# DM1098LUXD-LITE_RIGHT_OV7251.net
KiCad netlist of a schematic drawn in Altium Designer
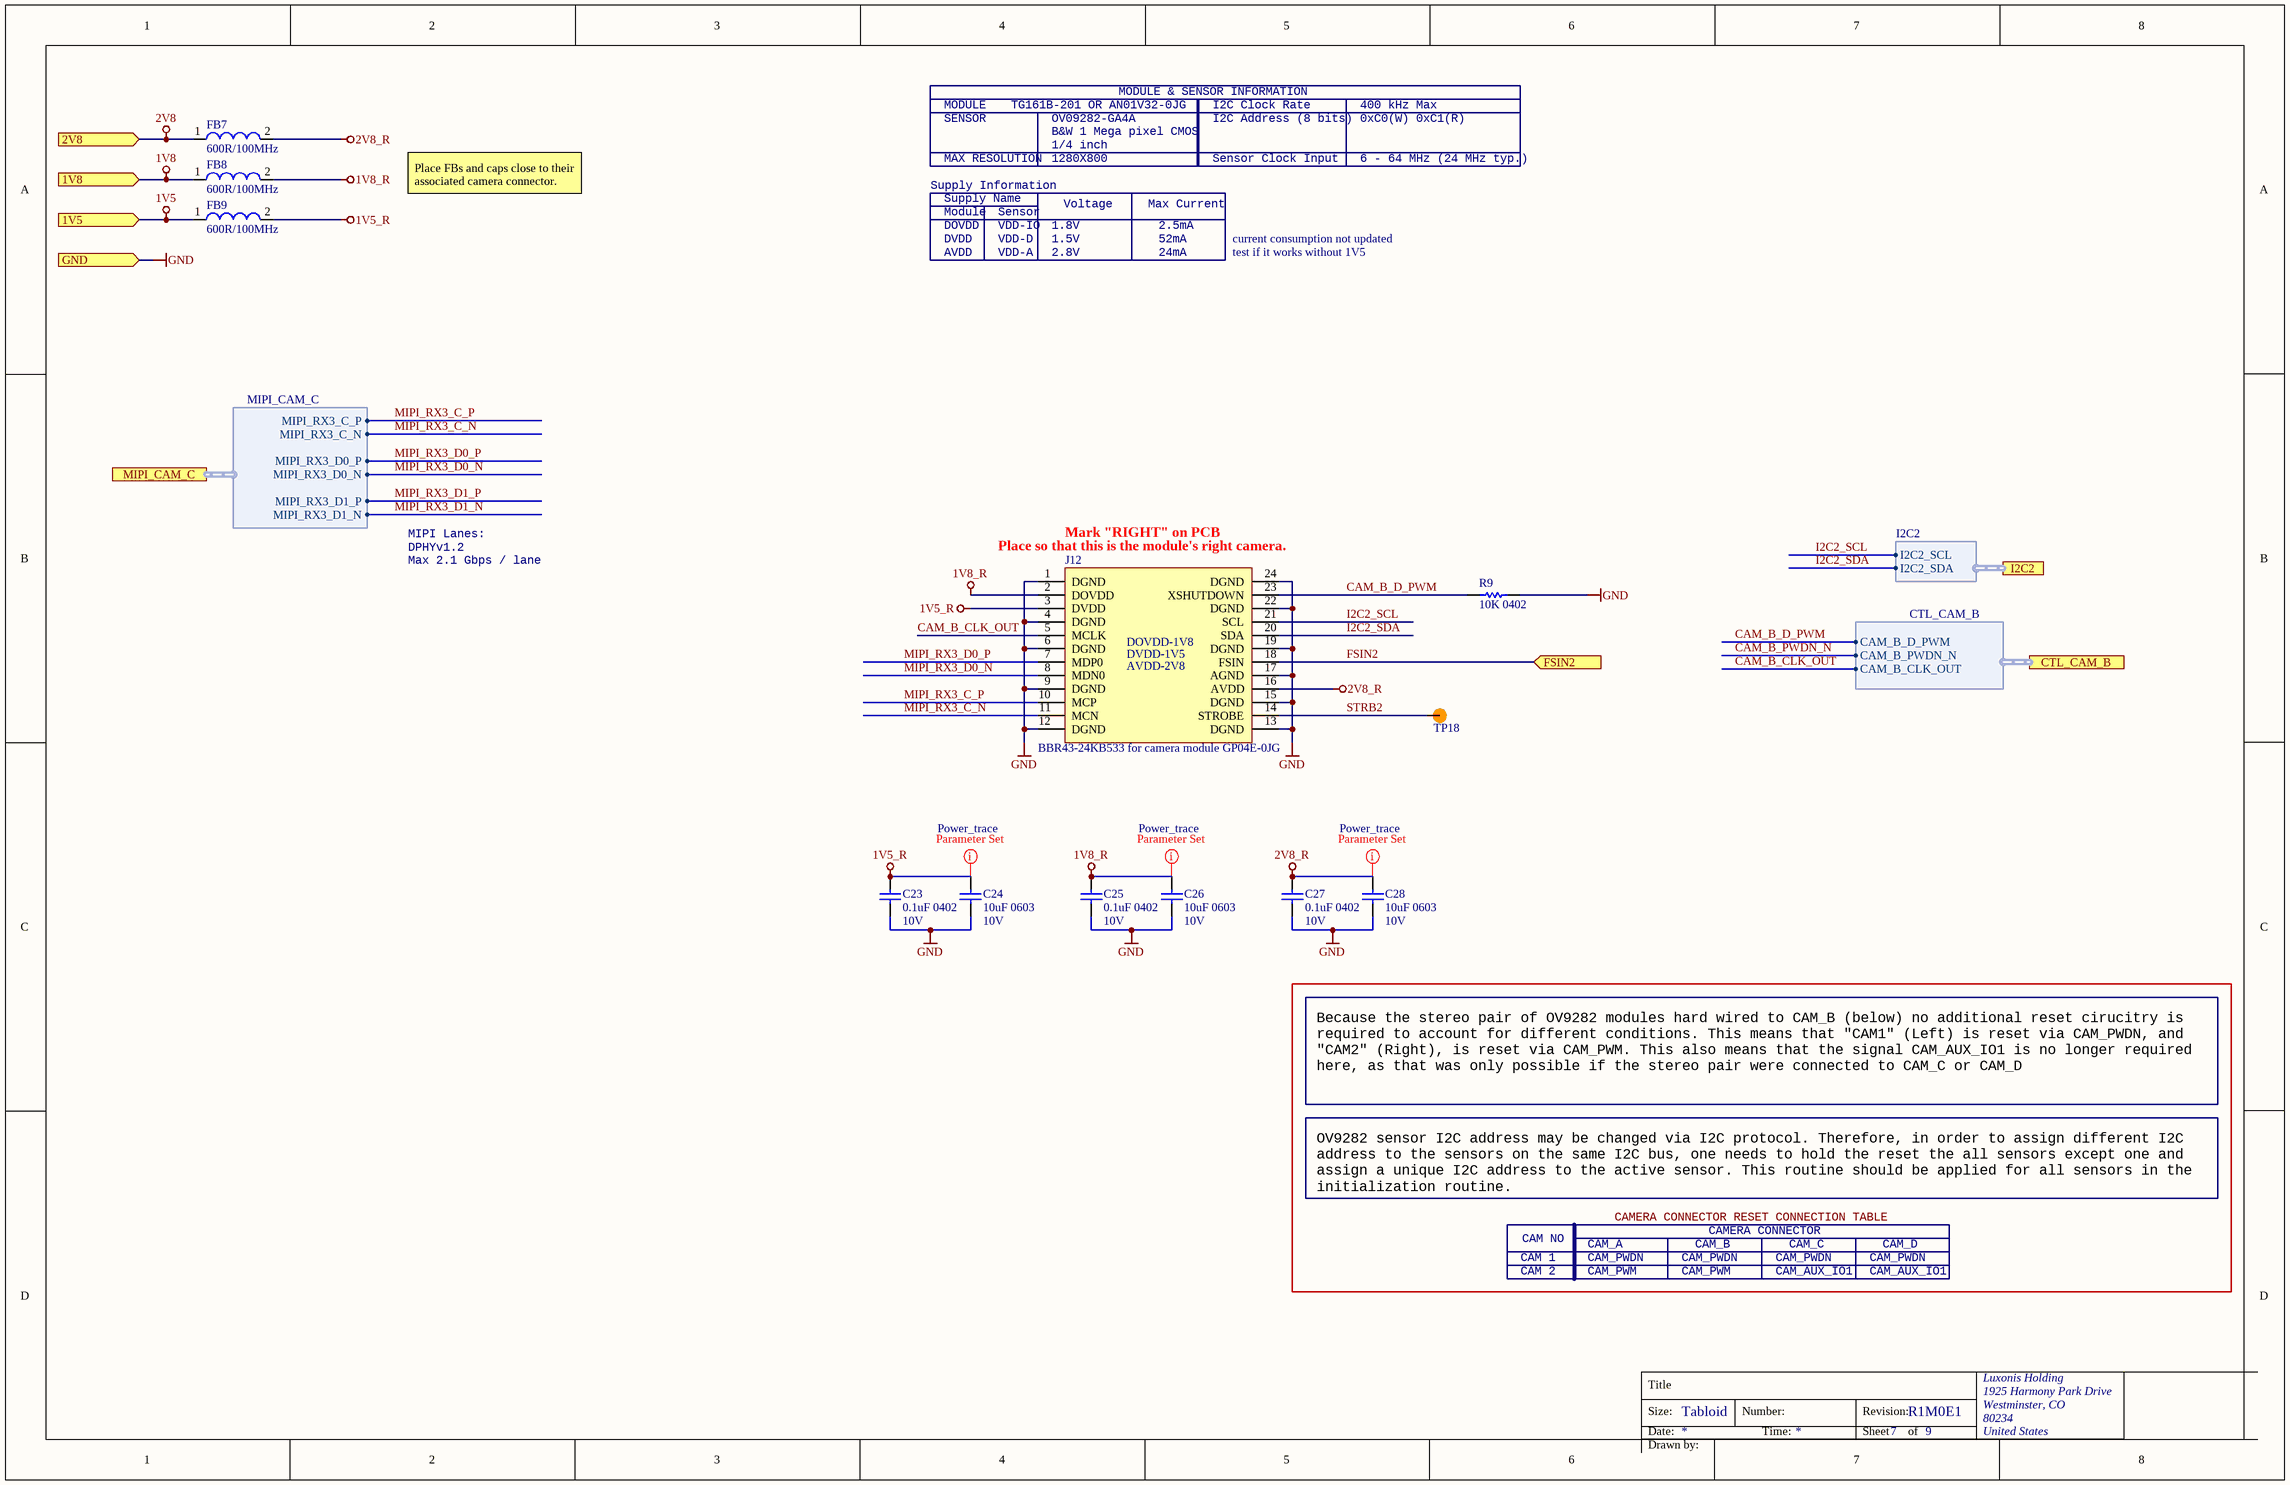
[diagram p0: DM1098LUXD-LITE_RIGHT_OV7251.SchDoc]

(export (version "E")
  (design (tool "Eeschema 10.0.6"))
  (components
    (comp (ref "C23")
      (value "0.1uF 0402")
      (footprint "CAP_Altium_Vault_Generic:CAPC0402(1005)70_L")
      (description "CAP CER 0.1UF 10V X7R 0402 5%")
      (fields (field (name "TOLERANCE") "5%") (field (name "VOLTAGE RATING") "10V"))
      (libsource (lib "LuxonisMaster") (part "GRM155R71A104JA01D"))
    )
    (comp (ref "C24")
      (value "10uF 0603")
      (footprint "CAP_Altium_Vault_Generic:CAPC0603(1608)100_L")
      (description "CAP CER 10UF 10V X5R 0603 20%")
      (fields (field (name "TOLERANCE") "20%") (field (name "VOLTAGE RATING") "10V"))
      (libsource (lib "LuxonisMaster") (part "GRM188R61A106ME69D"))
    )
    (comp (ref "C25")
      (value "0.1uF 0402")
      (footprint "CAP_Altium_Vault_Generic:CAPC0402(1005)70_L")
      (description "CAP CER 0.1UF 10V X7R 0402 5%")
      (fields (field (name "TOLERANCE") "5%") (field (name "VOLTAGE RATING") "10V"))
      (libsource (lib "LuxonisMaster") (part "GRM155R71A104JA01D"))
    )
    (comp (ref "C26")
      (value "10uF 0603")
      (footprint "CAP_Altium_Vault_Generic:CAPC0603(1608)100_L")
      (description "CAP CER 10UF 10V X5R 0603 20%")
      (fields (field (name "TOLERANCE") "20%") (field (name "VOLTAGE RATING") "10V"))
      (libsource (lib "LuxonisMaster") (part "GRM188R61A106ME69D"))
    )
    (comp (ref "C27")
      (value "0.1uF 0402")
      (footprint "CAP_Altium_Vault_Generic:CAPC0402(1005)70_L")
      (description "CAP CER 0.1UF 10V X7R 0402 5%")
      (fields (field (name "TOLERANCE") "5%") (field (name "VOLTAGE RATING") "10V"))
      (libsource (lib "LuxonisMaster") (part "GRM155R71A104JA01D"))
    )
    (comp (ref "C28")
      (value "10uF 0603")
      (footprint "CAP_Altium_Vault_Generic:CAPC0603(1608)100_L")
      (description "CAP CER 10UF 10V X5R 0603 20%")
      (fields (field (name "TOLERANCE") "20%") (field (name "VOLTAGE RATING") "10V"))
      (libsource (lib "LuxonisMaster") (part "GRM188R61A106ME69D"))
    )
    (comp (ref "FB7")
      (value "600R/100MHz")
      (footprint "LuxonisMaster:2508056017Y2")
      (description "FERRITE BEAD, 0.1OHM, 2A, 0805, 600R/100MHz")
      (fields (field (name "TOLERANCE") "25%"))
      (libsource (lib "LuxonisMaster") (part "2508056017Y2"))
    )
    (comp (ref "FB8")
      (value "600R/100MHz")
      (footprint "LuxonisMaster:2508056017Y2")
      (description "FERRITE BEAD, 0.1OHM, 2A, 0805, 600R/100MHz")
      (fields (field (name "TOLERANCE") "25%"))
      (libsource (lib "LuxonisMaster") (part "2508056017Y2"))
    )
    (comp (ref "FB9")
      (value "600R/100MHz")
      (footprint "LuxonisMaster:2508056017Y2")
      (description "FERRITE BEAD, 0.1OHM, 2A, 0805, 600R/100MHz")
      (fields (field (name "TOLERANCE") "25%"))
      (libsource (lib "LuxonisMaster") (part "2508056017Y2"))
    )
    (comp (ref "J12")
      (value "BBR43-24KB533 for camera module GP04E-0JG")
      (footprint "GP04E-0JG OV7251")
      (description "CONN 24 way, 2 row board to board connector SMD")
      (libsource (lib "DM1098LUXD-LITE") (part "GP04E-0JG_Connector"))
    )
    (comp (ref "R9")
      (value "10K 0402")
      (footprint "RES_Altium_Vault_Generic:RESC0402(1005)_L")
      (fields (field (name "TOLERANCE") "1%"))
      (libsource (lib "LuxonisMaster") (part "RC0402FR-1310KL"))
    )
    (comp (ref "TP18")
      (value "TP100_200_NS")
      (footprint "LuxonisMaster:TP100_200_NS")
      (libsource (lib "LuxonisMaster") (part "TEST_POINT"))
    )
  )
  (nets
    (net (code "4") (name "/CAM_B_CLK_OUT") (class "Default")
      (node (ref "J12") (pin "5") (pinfunction "MCLK_5") (pintype "passive"))
    )
    (net (code "5") (name "/CAM_B_D_PWM") (class "Default")
      (node (ref "J12") (pin "23") (pinfunction "XSHUTDOWN_23") (pintype "passive"))
      (node (ref "R9") (pin "1") (pinfunction "1_1") (pintype "passive"))
    )
    (net (code "7") (name "/FSIN2") (class "Default")
      (node (ref "J12") (pin "18") (pinfunction "FSIN_18") (pintype "passive"))
    )
    (net (code "8") (name "/I2C2_SCL") (class "Default")
      (node (ref "J12") (pin "21") (pinfunction "SCL_21") (pintype "passive"))
    )
    (net (code "9") (name "/I2C2_SDA") (class "Default")
      (node (ref "J12") (pin "20") (pinfunction "SDA_20") (pintype "passive"))
    )
    (net (code "10") (name "/MIPI_RX3_C_N") (class "Default")
      (node (ref "J12") (pin "11") (pinfunction "MCN_11") (pintype "passive"))
    )
    (net (code "11") (name "/MIPI_RX3_C_P") (class "Default")
      (node (ref "J12") (pin "10") (pinfunction "MCP_10") (pintype "passive"))
    )
    (net (code "12") (name "/MIPI_RX3_D0_N") (class "Default")
      (node (ref "J12") (pin "8") (pinfunction "MDN0_8") (pintype "passive"))
    )
    (net (code "13") (name "/MIPI_RX3_D0_P") (class "Default")
      (node (ref "J12") (pin "7") (pinfunction "MDP0_7") (pintype "passive"))
    )
    (net (code "16") (name "/STRB2") (class "Default")
      (node (ref "J12") (pin "14") (pinfunction "STROBE_14") (pintype "passive"))
      (node (ref "TP18") (pin "1") (pintype "passive"))
    )
    (net (code "20") (name "1V5") (class "Default")
      (node (ref "FB9") (pin "1") (pinfunction "1_1") (pintype "passive"))
    )
    (net (code "21") (name "1V5_R") (class "Default")
      (node (ref "C23") (pin "2") (pinfunction "2_2") (pintype "passive"))
      (node (ref "C24") (pin "2") (pinfunction "2_2") (pintype "passive"))
      (node (ref "FB9") (pin "2") (pinfunction "2_2") (pintype "passive"))
      (node (ref "J12") (pin "3") (pinfunction "DVDD_3") (pintype "passive"))
    )
    (net (code "22") (name "1V8") (class "Default")
      (node (ref "FB8") (pin "1") (pinfunction "1_1") (pintype "passive"))
    )
    (net (code "23") (name "1V8_R") (class "Default")
      (node (ref "C25") (pin "2") (pinfunction "2_2") (pintype "passive"))
      (node (ref "C26") (pin "2") (pinfunction "2_2") (pintype "passive"))
      (node (ref "FB8") (pin "2") (pinfunction "2_2") (pintype "passive"))
      (node (ref "J12") (pin "2") (pinfunction "DOVDD_2") (pintype "passive"))
    )
    (net (code "24") (name "2V8") (class "Default")
      (node (ref "FB7") (pin "1") (pinfunction "1_1") (pintype "passive"))
    )
    (net (code "25") (name "2V8_R") (class "Default")
      (node (ref "C27") (pin "2") (pinfunction "2_2") (pintype "passive"))
      (node (ref "C28") (pin "2") (pinfunction "2_2") (pintype "passive"))
      (node (ref "FB7") (pin "2") (pinfunction "2_2") (pintype "passive"))
      (node (ref "J12") (pin "16") (pinfunction "AVDD_16") (pintype "passive"))
    )
    (net (code "26") (name "GND") (class "Default")
      (node (ref "C23") (pin "1") (pinfunction "1_1") (pintype "passive"))
      (node (ref "C24") (pin "1") (pinfunction "1_1") (pintype "passive"))
      (node (ref "C25") (pin "1") (pinfunction "1_1") (pintype "passive"))
      (node (ref "C26") (pin "1") (pinfunction "1_1") (pintype "passive"))
      (node (ref "C27") (pin "1") (pinfunction "1_1") (pintype "passive"))
      (node (ref "C28") (pin "1") (pinfunction "1_1") (pintype "passive"))
      (node (ref "J12") (pin "1") (pinfunction "DGND_1") (pintype "passive"))
      (node (ref "J12") (pin "12") (pinfunction "DGND_12") (pintype "passive"))
      (node (ref "J12") (pin "13") (pinfunction "DGND_13") (pintype "passive"))
      (node (ref "J12") (pin "15") (pinfunction "DGND_15") (pintype "passive"))
      (node (ref "J12") (pin "17") (pinfunction "AGND_17") (pintype "passive"))
      (node (ref "J12") (pin "19") (pinfunction "DGND_19") (pintype "passive"))
      (node (ref "J12") (pin "22") (pinfunction "DGND_22") (pintype "passive"))
      (node (ref "J12") (pin "24") (pinfunction "DGND_24") (pintype "passive"))
      (node (ref "J12") (pin "4") (pinfunction "DGND_4") (pintype "passive"))
      (node (ref "J12") (pin "6") (pinfunction "DGND_6") (pintype "passive"))
      (node (ref "J12") (pin "9") (pinfunction "DGND_9") (pintype "passive"))
      (node (ref "R9") (pin "2") (pinfunction "2_2") (pintype "passive"))
    )
  )
)
